# DS3231.net
KiCad netlist of a schematic drawn in Altium Designer
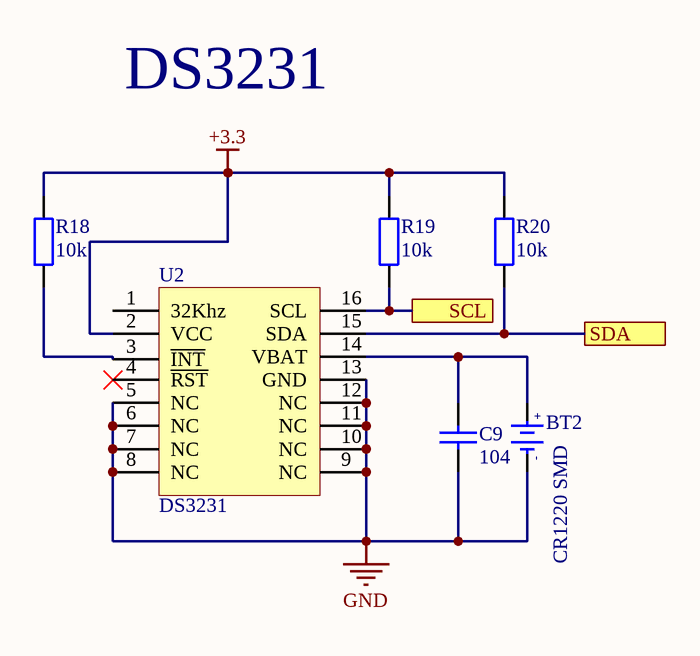
[diagram p0: DS3231.SchDoc]

(export (version "E")
  (design (tool "Eeschema 10.0.6"))
  (components
    (comp (ref "BT2")
      (value "CR1220 SMD")
      (footprint "DE PIN CR1220")
      (libsource (lib "Altium_Lib_by_KhueNguyenCreator") (part "De pin CR1220 SMD"))
    )
    (comp (ref "C9")
      (value "104")
      (footprint "tu 0603")
      (description "Dán")
      (libsource (lib "Altium_Lib_by_KhueNguyenCreator") (part "Tu 0603 104 50V 10%"))
    )
    (comp (ref "R18")
      (value "10k")
      (footprint "tro smd 0603")
      (description "Dán")
      (libsource (lib "Altium_Lib_by_KhueNguyenCreator") (part "Tro 0603 1% 10k"))
    )
    (comp (ref "R19")
      (value "10k")
      (footprint "tro smd 0603")
      (description "Dán")
      (libsource (lib "Altium_Lib_by_KhueNguyenCreator") (part "Tro 0603 1% 10k"))
    )
    (comp (ref "R20")
      (value "10k")
      (footprint "tro smd 0603")
      (description "Dán")
      (libsource (lib "Altium_Lib_by_KhueNguyenCreator") (part "Tro 0603 1% 10k"))
    )
    (comp (ref "U2")
      (value "DS3231")
      (footprint "SOIC 16")
      (description "SOIC")
      (libsource (lib "Altium_Lib_by_KhueNguyenCreator") (part "DS3231 SMD"))
    )
  )
  (nets
    (net (code "1") (name "+3.3") (class "Default")
      (node (ref "R18") (pin "2") (pinfunction "2_2") (pintype "passive"))
      (node (ref "R19") (pin "2") (pinfunction "2_2") (pintype "passive"))
      (node (ref "R20") (pin "2") (pinfunction "2_2") (pintype "passive"))
      (node (ref "U2") (pin "2") (pinfunction "VCC_2") (pintype "power_in"))
    )
    (net (code "2") (name "/SCL") (class "Default")
      (node (ref "R19") (pin "1") (pinfunction "1_1") (pintype "passive"))
      (node (ref "U2") (pin "16") (pinfunction "SCL_16") (pintype "power_in"))
    )
    (net (code "3") (name "/SDA") (class "Default")
      (node (ref "R20") (pin "1") (pinfunction "1_1") (pintype "passive"))
      (node (ref "U2") (pin "15") (pinfunction "SDA_15") (pintype "power_in"))
    )
    (net (code "4") (name "GND") (class "Default")
      (node (ref "BT2") (pin "2") (pinfunction "GND_2") (pintype "passive"))
      (node (ref "C9") (pin "2") (pinfunction "2_2") (pintype "passive"))
      (node (ref "U2") (pin "10") (pinfunction "NC_10") (pintype "power_in"))
      (node (ref "U2") (pin "11") (pinfunction "NC_11") (pintype "power_in"))
      (node (ref "U2") (pin "12") (pinfunction "NC_12") (pintype "power_in"))
      (node (ref "U2") (pin "13") (pinfunction "GND_13") (pintype "power_in"))
      (node (ref "U2") (pin "5") (pinfunction "NC_5") (pintype "power_in"))
      (node (ref "U2") (pin "6") (pinfunction "NC_6") (pintype "power_in"))
      (node (ref "U2") (pin "7") (pinfunction "NC_7") (pintype "power_in"))
      (node (ref "U2") (pin "8") (pinfunction "NC_8") (pintype "power_in"))
      (node (ref "U2") (pin "9") (pinfunction "NC_9") (pintype "power_in"))
    )
    (net (code "5") (name "Net-(BT2-+3V)") (class "Default")
      (node (ref "BT2") (pin "1") (pinfunction "+3V_1") (pintype "passive"))
      (node (ref "C9") (pin "1") (pinfunction "1_1") (pintype "passive"))
      (node (ref "U2") (pin "14") (pinfunction "VBAT_14") (pintype "power_in"))
    )
    (net (code "6") (name "Net-(U2-~{INT})") (class "Default")
      (node (ref "R18") (pin "1") (pinfunction "1_1") (pintype "passive"))
      (node (ref "U2") (pin "3") (pinfunction "~{INT}_3") (pintype "power_in"))
    )
    (net (code "7") (name "unconnected-(U2-32Khz-Pad1)") (class "Default")
      (node (ref "U2") (pin "1") (pinfunction "32Khz_1") (pintype "power_in"))
    )
    (net (code "8") (name "unconnected-(U2-~{RST}-Pad4)") (class "Default")
      (node (ref "U2") (pin "4") (pinfunction "~{RST}_4") (pintype "power_in+no_connect"))
    )
  )
)
